# a405-diode-distortion.net
KiCad netlist of a schematic drawn in EAGLE
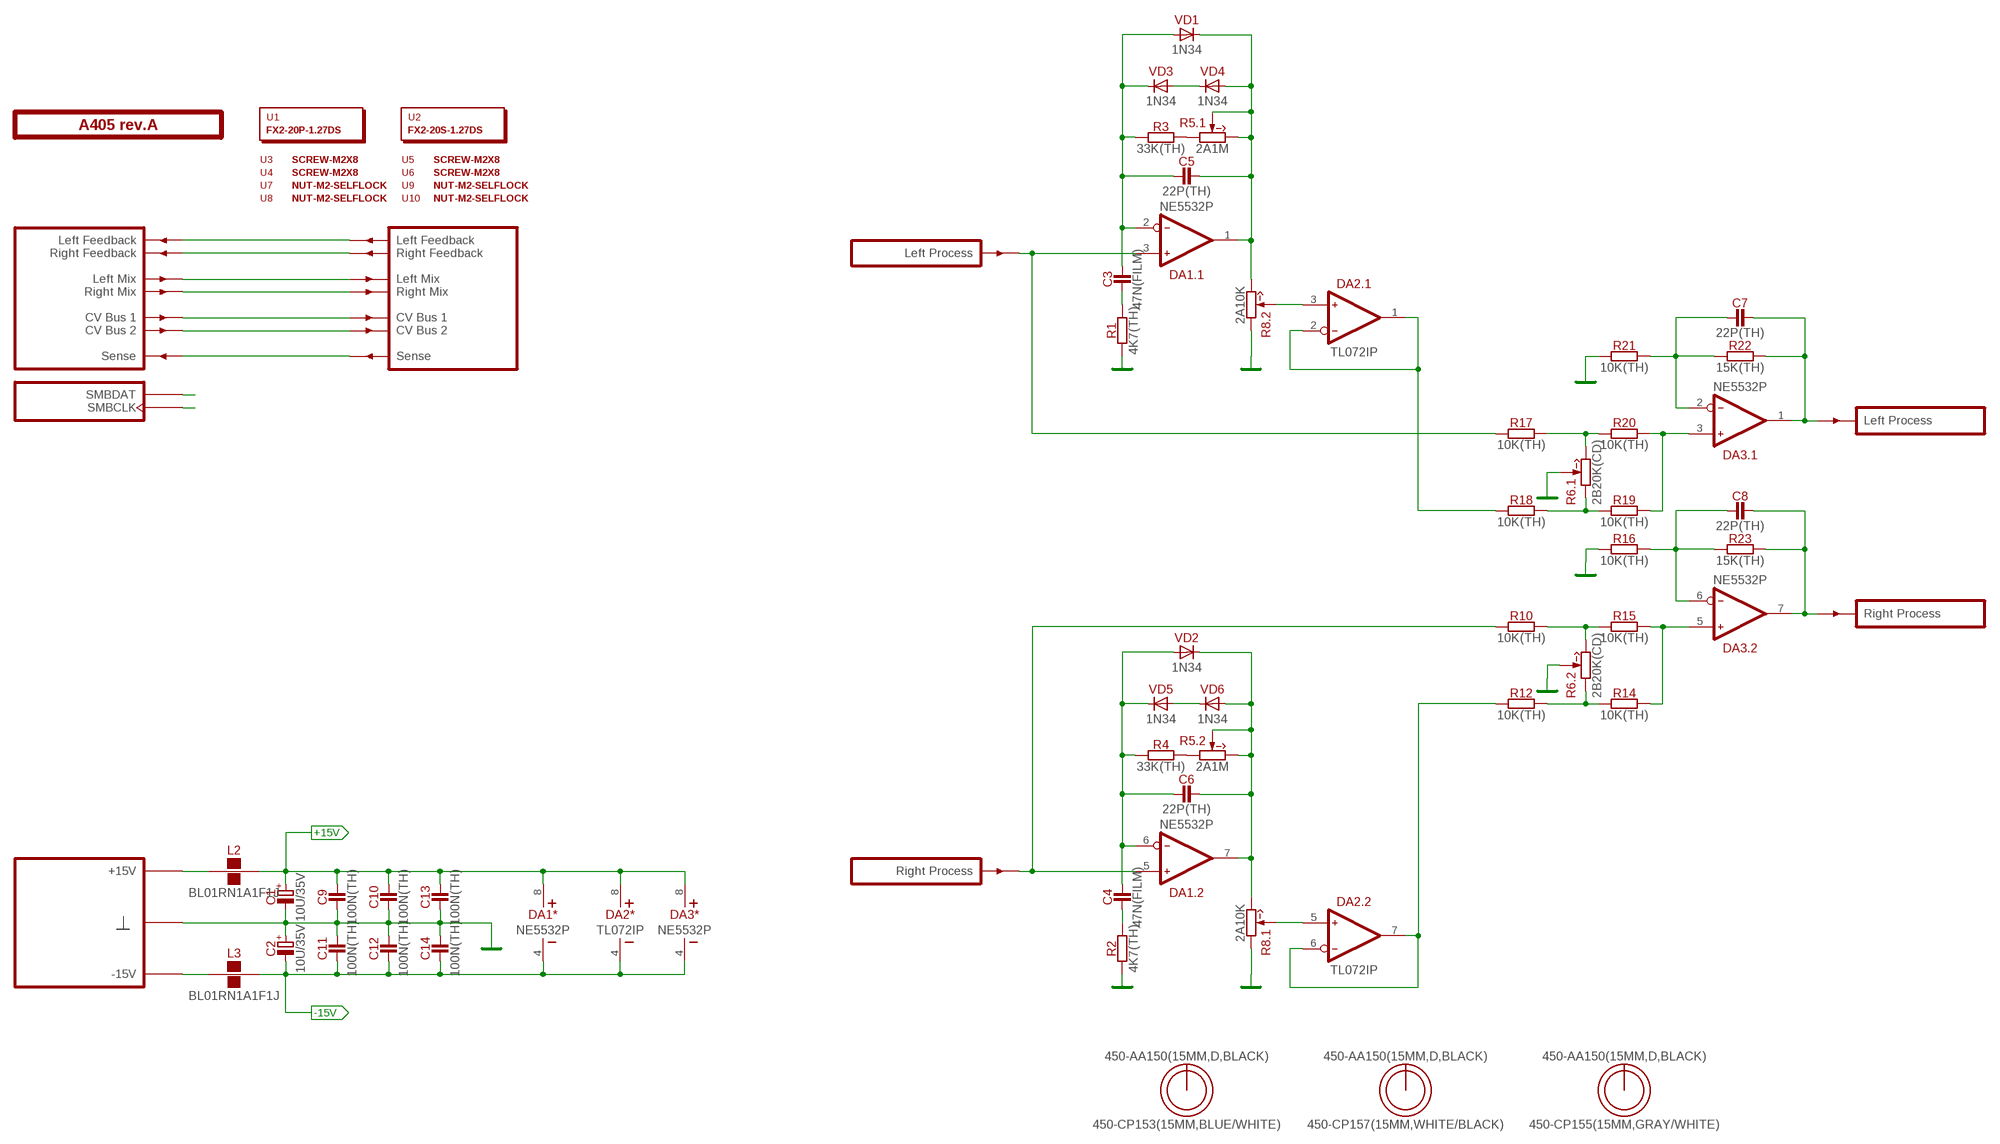
[diagram p0: schematic, sheet 1]

(export (version "E")
  (design (tool "Eeschema 10.0.6"))
  (components
    (comp (ref "C1")
      (value "10U/35V")
      (footprint "eagle-import:E2-5")
      (libsource (lib "eagle-import") (part "?10U/35V"))
    )
    (comp (ref "C2")
      (value "10U/35V")
      (footprint "eagle-import:E2-5")
      (libsource (lib "eagle-import") (part "?10U/35V"))
    )
    (comp (ref "C3")
      (value "47N(FILM)")
      (footprint "eagle-import:C050-025X075")
      (libsource (lib "eagle-import") (part "?47N(FILM)"))
    )
    (comp (ref "C4")
      (value "47N(FILM)")
      (footprint "eagle-import:C050-025X075")
      (libsource (lib "eagle-import") (part "?47N(FILM)"))
    )
    (comp (ref "C5")
      (value "22P(TH)")
      (footprint "eagle-import:C050-024X044")
      (libsource (lib "eagle-import") (part "?22P(TH)"))
    )
    (comp (ref "C6")
      (value "22P(TH)")
      (footprint "eagle-import:C050-024X044")
      (libsource (lib "eagle-import") (part "?22P(TH)"))
    )
    (comp (ref "C7")
      (value "22P(TH)")
      (footprint "eagle-import:C050-024X044")
      (libsource (lib "eagle-import") (part "?22P(TH)"))
    )
    (comp (ref "C8")
      (value "22P(TH)")
      (footprint "eagle-import:C050-024X044")
      (libsource (lib "eagle-import") (part "?22P(TH)"))
    )
    (comp (ref "C9")
      (value "100N(TH)")
      (footprint "eagle-import:C050-024X044")
      (libsource (lib "eagle-import") (part "?100N(TH)"))
    )
    (comp (ref "C10")
      (value "100N(TH)")
      (footprint "eagle-import:C050-024X044")
      (libsource (lib "eagle-import") (part "?100N(TH)"))
    )
    (comp (ref "C11")
      (value "100N(TH)")
      (footprint "eagle-import:C050-024X044")
      (libsource (lib "eagle-import") (part "?100N(TH)"))
    )
    (comp (ref "C12")
      (value "100N(TH)")
      (footprint "eagle-import:C050-024X044")
      (libsource (lib "eagle-import") (part "?100N(TH)"))
    )
    (comp (ref "C13")
      (value "100N(TH)")
      (footprint "eagle-import:C050-024X044")
      (libsource (lib "eagle-import") (part "?100N(TH)"))
    )
    (comp (ref "C14")
      (value "100N(TH)")
      (footprint "eagle-import:C050-024X044")
      (libsource (lib "eagle-import") (part "?100N(TH)"))
    )
    (comp (ref "DA1")
      (value "NE5532P")
      (footprint "eagle-import:DIP-8")
      (libsource (lib "eagle-import") (part "NE5532P"))
    )
    (comp (ref "DA2")
      (value "TL072IP")
      (footprint "eagle-import:DIP-8")
      (libsource (lib "eagle-import") (part "TL072IP"))
    )
    (comp (ref "DA3")
      (value "NE5532P")
      (footprint "eagle-import:DIP-8")
      (libsource (lib "eagle-import") (part "NE5532P"))
    )
    (comp (ref "L2")
      (value "BL01RN1A1F1J")
      (footprint "eagle-import:BL01RN1A")
      (libsource (lib "eagle-import") (part "BL01RN1A?1F1J"))
    )
    (comp (ref "L3")
      (value "BL01RN1A1F1J")
      (footprint "eagle-import:BL01RN1A")
      (libsource (lib "eagle-import") (part "BL01RN1A?1F1J"))
    )
    (comp (ref "O2")
      (value "450-AA150(15MM,D,BLACK)")
      (footprint "eagle-import:EMPTY")
      (libsource (lib "eagle-import") (part "450-AA?150(15MM,D,BLACK)"))
    )
    (comp (ref "O3")
      (value "450-AA150(15MM,D,BLACK)")
      (footprint "eagle-import:EMPTY")
      (libsource (lib "eagle-import") (part "450-AA?150(15MM,D,BLACK)"))
    )
    (comp (ref "O4")
      (value "450-AA150(15MM,D,BLACK)")
      (footprint "eagle-import:EMPTY")
      (libsource (lib "eagle-import") (part "450-AA?150(15MM,D,BLACK)"))
    )
    (comp (ref "O5")
      (value "450-CP155(15MM,GRAY/WHITE)")
      (footprint "eagle-import:EMPTY")
      (libsource (lib "eagle-import") (part "450-C?P155(15MM,GRAY/WHITE)"))
    )
    (comp (ref "O6")
      (value "450-CP157(15MM,WHITE/BLACK)")
      (footprint "eagle-import:EMPTY")
      (libsource (lib "eagle-import") (part "450-C?P157(15MM,WHITE/BLACK)"))
    )
    (comp (ref "O7")
      (value "450-CP153(15MM,BLUE/WHITE)")
      (footprint "eagle-import:EMPTY")
      (libsource (lib "eagle-import") (part "450-C?P153(15MM,BLUE/WHITE)"))
    )
    (comp (ref "PCB1")
      (value "A405 rev.A")
      (footprint "eagle-import:ST2-BOARD-50")
      (libsource (lib "eagle-import") (part "ST2-BOARD-?50"))
    )
    (comp (ref "R1")
      (value "4K7(TH)")
      (footprint "eagle-import:R-0207_10")
      (libsource (lib "eagle-import") (part "?4K7(TH)"))
    )
    (comp (ref "R2")
      (value "4K7(TH)")
      (footprint "eagle-import:R-0207_10")
      (libsource (lib "eagle-import") (part "?4K7(TH)"))
    )
    (comp (ref "R3")
      (value "33K(TH)")
      (footprint "eagle-import:R-0207_10")
      (libsource (lib "eagle-import") (part "?33K(TH)"))
    )
    (comp (ref "R4")
      (value "33K(TH)")
      (footprint "eagle-import:R-0207_10")
      (libsource (lib "eagle-import") (part "?33K(TH)"))
    )
    (comp (ref "R5")
      (value "2A1M")
      (footprint "eagle-import:RV11-DUAL")
      (libsource (lib "eagle-import") (part "2?A1M"))
    )
    (comp (ref "R6")
      (value "2B20K(CD)")
      (footprint "eagle-import:RV11-DUAL")
      (libsource (lib "eagle-import") (part "2?B20K(CD)"))
    )
    (comp (ref "R8")
      (value "2A10K")
      (footprint "eagle-import:RV11-DUAL")
      (libsource (lib "eagle-import") (part "2?A10K"))
    )
    (comp (ref "R10")
      (value "10K(TH)")
      (footprint "eagle-import:R-0207_10")
      (libsource (lib "eagle-import") (part "?10K(TH)"))
    )
    (comp (ref "R12")
      (value "10K(TH)")
      (footprint "eagle-import:R-0207_10")
      (libsource (lib "eagle-import") (part "?10K(TH)"))
    )
    (comp (ref "R14")
      (value "10K(TH)")
      (footprint "eagle-import:R-0207_10")
      (libsource (lib "eagle-import") (part "?10K(TH)"))
    )
    (comp (ref "R15")
      (value "10K(TH)")
      (footprint "eagle-import:R-0207_10")
      (libsource (lib "eagle-import") (part "?10K(TH)"))
    )
    (comp (ref "R16")
      (value "10K(TH)")
      (footprint "eagle-import:R-0207_10")
      (libsource (lib "eagle-import") (part "?10K(TH)"))
    )
    (comp (ref "R17")
      (value "10K(TH)")
      (footprint "eagle-import:R-0207_10")
      (libsource (lib "eagle-import") (part "?10K(TH)"))
    )
    (comp (ref "R18")
      (value "10K(TH)")
      (footprint "eagle-import:R-0207_10")
      (libsource (lib "eagle-import") (part "?10K(TH)"))
    )
    (comp (ref "R19")
      (value "10K(TH)")
      (footprint "eagle-import:R-0207_10")
      (libsource (lib "eagle-import") (part "?10K(TH)"))
    )
    (comp (ref "R20")
      (value "10K(TH)")
      (footprint "eagle-import:R-0207_10")
      (libsource (lib "eagle-import") (part "?10K(TH)"))
    )
    (comp (ref "R21")
      (value "10K(TH)")
      (footprint "eagle-import:R-0207_10")
      (libsource (lib "eagle-import") (part "?10K(TH)"))
    )
    (comp (ref "R22")
      (value "15K(TH)")
      (footprint "eagle-import:R-0207_10")
      (libsource (lib "eagle-import") (part "?15K(TH)"))
    )
    (comp (ref "R23")
      (value "15K(TH)")
      (footprint "eagle-import:R-0207_10")
      (libsource (lib "eagle-import") (part "?15K(TH)"))
    )
    (comp (ref "U1")
      (value "FX2-20P-1.27DS")
      (footprint "eagle-import:EMPTY")
      (libsource (lib "eagle-import") (part "?FX2-20P-1.27DS"))
    )
    (comp (ref "U2")
      (value "FX2-20S-1.27DS")
      (footprint "eagle-import:EMPTY")
      (libsource (lib "eagle-import") (part "?FX2-20S-1.27DS"))
    )
    (comp (ref "U3")
      (value "SCREW-M2X8")
      (footprint "eagle-import:EMPTY")
      (libsource (lib "eagle-import") (part "?SCREW-M2X8"))
    )
    (comp (ref "U4")
      (value "SCREW-M2X8")
      (footprint "eagle-import:EMPTY")
      (libsource (lib "eagle-import") (part "?SCREW-M2X8"))
    )
    (comp (ref "U5")
      (value "SCREW-M2X8")
      (footprint "eagle-import:EMPTY")
      (libsource (lib "eagle-import") (part "?SCREW-M2X8"))
    )
    (comp (ref "U6")
      (value "SCREW-M2X8")
      (footprint "eagle-import:EMPTY")
      (libsource (lib "eagle-import") (part "?SCREW-M2X8"))
    )
    (comp (ref "U7")
      (value "NUT-M2-SELFLOCK")
      (footprint "eagle-import:EMPTY")
      (libsource (lib "eagle-import") (part "?NUT-M2-SELFLOCK"))
    )
    (comp (ref "U8")
      (value "NUT-M2-SELFLOCK")
      (footprint "eagle-import:EMPTY")
      (libsource (lib "eagle-import") (part "?NUT-M2-SELFLOCK"))
    )
    (comp (ref "U9")
      (value "NUT-M2-SELFLOCK")
      (footprint "eagle-import:EMPTY")
      (libsource (lib "eagle-import") (part "?NUT-M2-SELFLOCK"))
    )
    (comp (ref "U10")
      (value "NUT-M2-SELFLOCK")
      (footprint "eagle-import:EMPTY")
      (libsource (lib "eagle-import") (part "?NUT-M2-SELFLOCK"))
    )
    (comp (ref "VD1")
      (value "1N34")
      (footprint "eagle-import:DO35-15")
      (libsource (lib "eagle-import") (part "?1N34"))
    )
    (comp (ref "VD2")
      (value "1N34")
      (footprint "eagle-import:DO35-15")
      (libsource (lib "eagle-import") (part "?1N34"))
    )
    (comp (ref "VD3")
      (value "1N34")
      (footprint "eagle-import:DO35-15")
      (libsource (lib "eagle-import") (part "?1N34"))
    )
    (comp (ref "VD4")
      (value "1N34")
      (footprint "eagle-import:DO35-15")
      (libsource (lib "eagle-import") (part "?1N34"))
    )
    (comp (ref "VD5")
      (value "1N34")
      (footprint "eagle-import:DO35-15")
      (libsource (lib "eagle-import") (part "?1N34"))
    )
    (comp (ref "VD6")
      (value "1N34")
      (footprint "eagle-import:DO35-15")
      (libsource (lib "eagle-import") (part "?1N34"))
    )
  )
  (nets
    (net (code "1") (name "+15V") (class "Default")
      (node (ref "C1") (pin "+") (pinfunction "+_+") (pintype "passive"))
      (node (ref "C10") (pin "2") (pinfunction "2_2") (pintype "passive"))
      (node (ref "C13") (pin "2") (pinfunction "2_2") (pintype "passive"))
      (node (ref "C9") (pin "2") (pinfunction "2_2") (pintype "passive"))
      (node (ref "DA1") (pin "8") (pinfunction "V+_8") (pintype "power_in"))
      (node (ref "DA2") (pin "8") (pinfunction "V+_8") (pintype "power_in"))
      (node (ref "DA3") (pin "8") (pinfunction "V+_8") (pintype "power_in"))
      (node (ref "L2") (pin "2") (pinfunction "2_2") (pintype "passive"))
    )
    (net (code "2") (name "-15V") (class "Default")
      (node (ref "C11") (pin "1") (pinfunction "1_1") (pintype "passive"))
      (node (ref "C12") (pin "1") (pinfunction "1_1") (pintype "passive"))
      (node (ref "C14") (pin "1") (pinfunction "1_1") (pintype "passive"))
      (node (ref "C2") (pin "-") (pinfunction "-_-") (pintype "passive"))
      (node (ref "DA1") (pin "4") (pinfunction "V-_4") (pintype "power_in"))
      (node (ref "DA2") (pin "4") (pinfunction "V-_4") (pintype "power_in"))
      (node (ref "DA3") (pin "4") (pinfunction "V-_4") (pintype "power_in"))
      (node (ref "L3") (pin "2") (pinfunction "2_2") (pintype "passive"))
    )
    (net (code "3") (name "GND") (class "Default")
      (node (ref "C1") (pin "-") (pinfunction "-_-") (pintype "passive"))
      (node (ref "C10") (pin "1") (pinfunction "1_1") (pintype "passive"))
      (node (ref "C11") (pin "2") (pinfunction "2_2") (pintype "passive"))
      (node (ref "C12") (pin "2") (pinfunction "2_2") (pintype "passive"))
      (node (ref "C13") (pin "1") (pinfunction "1_1") (pintype "passive"))
      (node (ref "C14") (pin "2") (pinfunction "2_2") (pintype "passive"))
      (node (ref "C2") (pin "+") (pinfunction "+_+") (pintype "passive"))
      (node (ref "C9") (pin "1") (pinfunction "1_1") (pintype "passive"))
      (node (ref "PCB1") (pin "B4") (pinfunction "GND_B4") (pintype "bidirectional"))
      (node (ref "PCB1") (pin "B4'") (pinfunction "GND_B4'") (pintype "bidirectional"))
      (node (ref "PCB1") (pin "B5") (pinfunction "GND_B5") (pintype "bidirectional"))
      (node (ref "PCB1") (pin "B5'") (pinfunction "GND_B5'") (pintype "bidirectional"))
      (node (ref "PCB1") (pin "B6") (pinfunction "GND_B6") (pintype "bidirectional"))
      (node (ref "PCB1") (pin "B6'") (pinfunction "GND_B6'") (pintype "bidirectional"))
      (node (ref "PCB1") (pin "B7") (pinfunction "GND_B7") (pintype "bidirectional"))
      (node (ref "PCB1") (pin "B7'") (pinfunction "GND_B7'") (pintype "bidirectional"))
      (node (ref "PCB1") (pin "B8") (pinfunction "GND_B8") (pintype "bidirectional"))
      (node (ref "PCB1") (pin "B8'") (pinfunction "GND_B8'") (pintype "bidirectional"))
      (node (ref "R1") (pin "1") (pinfunction "1_1") (pintype "passive"))
      (node (ref "R16") (pin "1") (pinfunction "1_1") (pintype "passive"))
      (node (ref "R2") (pin "1") (pinfunction "1_1") (pintype "passive"))
      (node (ref "R21") (pin "1") (pinfunction "1_1") (pintype "passive"))
      (node (ref "R6") (pin "2") (pinfunction "W_2") (pintype "passive"))
      (node (ref "R6") (pin "2'") (pinfunction "W_2'") (pintype "passive"))
      (node (ref "R8") (pin "1") (pinfunction "CCW_1") (pintype "passive"))
      (node (ref "R8") (pin "1'") (pinfunction "CCW_1'") (pintype "passive"))
    )
    (net (code "4") (name "Net-(C3-Pad1)") (class "Default")
      (node (ref "C3") (pin "1") (pinfunction "1_1") (pintype "passive"))
      (node (ref "R1") (pin "2") (pinfunction "2_2") (pintype "passive"))
    )
    (net (code "5") (name "Net-(C4-Pad1)") (class "Default")
      (node (ref "C4") (pin "1") (pinfunction "1_1") (pintype "passive"))
      (node (ref "R2") (pin "2") (pinfunction "2_2") (pintype "passive"))
    )
    (net (code "6") (name "Net-(DA1B-IN+)") (class "Default")
      (node (ref "DA1") (pin "3") (pinfunction "IN+_3") (pintype "input"))
      (node (ref "PCB1") (pin "BINL") (pinfunction "INL_BINL") (pintype "bidirectional"))
      (node (ref "R17") (pin "1") (pinfunction "1_1") (pintype "passive"))
    )
    (net (code "7") (name "Net-(DA1B-IN-)") (class "Default")
      (node (ref "C3") (pin "2") (pinfunction "2_2") (pintype "passive"))
      (node (ref "C5") (pin "1") (pinfunction "1_1") (pintype "passive"))
      (node (ref "DA1") (pin "2") (pinfunction "IN-_2") (pintype "input"))
      (node (ref "R3") (pin "1") (pinfunction "1_1") (pintype "passive"))
      (node (ref "VD1") (pin "A") (pinfunction "A_A") (pintype "passive"))
      (node (ref "VD3") (pin "C") (pinfunction "C_C") (pintype "passive"))
    )
    (net (code "8") (name "Net-(DA1B-OUT)") (class "Default")
      (node (ref "C5") (pin "2") (pinfunction "2_2") (pintype "passive"))
      (node (ref "DA1") (pin "1") (pinfunction "OUT_1") (pintype "output"))
      (node (ref "R5") (pin "2") (pinfunction "W_2") (pintype "passive"))
      (node (ref "R5") (pin "3") (pinfunction "CW_3") (pintype "passive"))
      (node (ref "R8") (pin "3'") (pinfunction "CW_3'") (pintype "passive"))
      (node (ref "VD1") (pin "C") (pinfunction "C_C") (pintype "passive"))
      (node (ref "VD4") (pin "A") (pinfunction "A_A") (pintype "passive"))
    )
    (net (code "9") (name "Net-(DA1C-IN+)") (class "Default")
      (node (ref "DA1") (pin "5") (pinfunction "IN+_5") (pintype "input"))
      (node (ref "PCB1") (pin "BINR") (pinfunction "INR_BINR") (pintype "bidirectional"))
      (node (ref "R10") (pin "1") (pinfunction "1_1") (pintype "passive"))
    )
    (net (code "10") (name "Net-(DA1C-IN-)") (class "Default")
      (node (ref "C4") (pin "2") (pinfunction "2_2") (pintype "passive"))
      (node (ref "C6") (pin "1") (pinfunction "1_1") (pintype "passive"))
      (node (ref "DA1") (pin "6") (pinfunction "IN-_6") (pintype "input"))
      (node (ref "R4") (pin "1") (pinfunction "1_1") (pintype "passive"))
      (node (ref "VD2") (pin "A") (pinfunction "A_A") (pintype "passive"))
      (node (ref "VD5") (pin "C") (pinfunction "C_C") (pintype "passive"))
    )
    (net (code "11") (name "Net-(DA1C-OUT)") (class "Default")
      (node (ref "C6") (pin "2") (pinfunction "2_2") (pintype "passive"))
      (node (ref "DA1") (pin "7") (pinfunction "OUT_7") (pintype "output"))
      (node (ref "R5") (pin "2'") (pinfunction "W_2'") (pintype "passive"))
      (node (ref "R5") (pin "3'") (pinfunction "CW_3'") (pintype "passive"))
      (node (ref "R8") (pin "3") (pinfunction "CW_3") (pintype "passive"))
      (node (ref "VD2") (pin "C") (pinfunction "C_C") (pintype "passive"))
      (node (ref "VD6") (pin "A") (pinfunction "A_A") (pintype "passive"))
    )
    (net (code "12") (name "Net-(DA2B-IN+)") (class "Default")
      (node (ref "DA2") (pin "3") (pinfunction "IN+_3") (pintype "input"))
      (node (ref "R8") (pin "2'") (pinfunction "W_2'") (pintype "passive"))
    )
    (net (code "13") (name "Net-(DA2B-IN-)") (class "Default")
      (node (ref "DA2") (pin "1") (pinfunction "OUT_1") (pintype "output"))
      (node (ref "DA2") (pin "2") (pinfunction "IN-_2") (pintype "input"))
      (node (ref "R18") (pin "1") (pinfunction "1_1") (pintype "passive"))
    )
    (net (code "14") (name "Net-(DA2C-IN+)") (class "Default")
      (node (ref "DA2") (pin "5") (pinfunction "IN+_5") (pintype "input"))
      (node (ref "R8") (pin "2") (pinfunction "W_2") (pintype "passive"))
    )
    (net (code "15") (name "Net-(DA2C-IN-)") (class "Default")
      (node (ref "DA2") (pin "6") (pinfunction "IN-_6") (pintype "input"))
      (node (ref "DA2") (pin "7") (pinfunction "OUT_7") (pintype "output"))
      (node (ref "R12") (pin "1") (pinfunction "1_1") (pintype "passive"))
    )
    (net (code "16") (name "Net-(DA3B-IN+)") (class "Default")
      (node (ref "DA3") (pin "3") (pinfunction "IN+_3") (pintype "input"))
      (node (ref "R19") (pin "2") (pinfunction "2_2") (pintype "passive"))
      (node (ref "R20") (pin "2") (pinfunction "2_2") (pintype "passive"))
    )
    (net (code "17") (name "Net-(DA3B-IN-)") (class "Default")
      (node (ref "C7") (pin "1") (pinfunction "1_1") (pintype "passive"))
      (node (ref "DA3") (pin "2") (pinfunction "IN-_2") (pintype "input"))
      (node (ref "R21") (pin "2") (pinfunction "2_2") (pintype "passive"))
      (node (ref "R22") (pin "1") (pinfunction "1_1") (pintype "passive"))
    )
    (net (code "18") (name "Net-(DA3B-OUT)") (class "Default")
      (node (ref "C7") (pin "2") (pinfunction "2_2") (pintype "passive"))
      (node (ref "DA3") (pin "1") (pinfunction "OUT_1") (pintype "output"))
      (node (ref "PCB1") (pin "BOUTL'") (pinfunction "OUTL_BOUTL'") (pintype "bidirectional"))
      (node (ref "R22") (pin "2") (pinfunction "2_2") (pintype "passive"))
    )
    (net (code "19") (name "Net-(DA3C-IN+)") (class "Default")
      (node (ref "DA3") (pin "5") (pinfunction "IN+_5") (pintype "input"))
      (node (ref "R14") (pin "2") (pinfunction "2_2") (pintype "passive"))
      (node (ref "R15") (pin "2") (pinfunction "2_2") (pintype "passive"))
    )
    (net (code "20") (name "Net-(DA3C-IN-)") (class "Default")
      (node (ref "C8") (pin "1") (pinfunction "1_1") (pintype "passive"))
      (node (ref "DA3") (pin "6") (pinfunction "IN-_6") (pintype "input"))
      (node (ref "R16") (pin "2") (pinfunction "2_2") (pintype "passive"))
      (node (ref "R23") (pin "1") (pinfunction "1_1") (pintype "passive"))
    )
    (net (code "21") (name "Net-(DA3C-OUT)") (class "Default")
      (node (ref "C8") (pin "2") (pinfunction "2_2") (pintype "passive"))
      (node (ref "DA3") (pin "7") (pinfunction "OUT_7") (pintype "output"))
      (node (ref "PCB1") (pin "BOUTR'") (pinfunction "OUTR_BOUTR'") (pintype "bidirectional"))
      (node (ref "R23") (pin "2") (pinfunction "2_2") (pintype "passive"))
    )
    (net (code "22") (name "Net-(L2-Pad1)") (class "Default")
      (node (ref "L2") (pin "1") (pinfunction "1_1") (pintype "passive"))
      (node (ref "PCB1") (pin "A+15") (pinfunction "P+15V_A+15") (pintype "bidirectional"))
      (node (ref "PCB1") (pin "A+15'") (pinfunction "P+15V_A+15'") (pintype "bidirectional"))
      (node (ref "PCB1") (pin "B+15") (pinfunction "P+15V_B+15") (pintype "bidirectional"))
      (node (ref "PCB1") (pin "B+15'") (pinfunction "P+15V_B+15'") (pintype "bidirectional"))
    )
    (net (code "23") (name "Net-(L3-Pad1)") (class "Default")
      (node (ref "L3") (pin "1") (pinfunction "1_1") (pintype "passive"))
      (node (ref "PCB1") (pin "A-15") (pinfunction "P-15V_A-15") (pintype "bidirectional"))
      (node (ref "PCB1") (pin "A-15'") (pinfunction "P-15V_A-15'") (pintype "bidirectional"))
      (node (ref "PCB1") (pin "B-15") (pinfunction "P-15V_B-15") (pintype "bidirectional"))
      (node (ref "PCB1") (pin "B-15'") (pinfunction "P-15V_B-15'") (pintype "bidirectional"))
    )
    (net (code "24") (name "Net-(PCB1F-CV1)") (class "Default")
      (node (ref "PCB1") (pin "ACV1") (pinfunction "CV1_ACV1") (pintype "bidirectional"))
      (node (ref "PCB1") (pin "ACV1'") (pinfunction "CV1'_ACV1'") (pintype "bidirectional"))
    )
    (net (code "25") (name "Net-(PCB1F-CV2)") (class "Default")
      (node (ref "PCB1") (pin "ACV2") (pinfunction "CV2_ACV2") (pintype "bidirectional"))
      (node (ref "PCB1") (pin "ACV2'") (pinfunction "CV2'_ACV2'") (pintype "bidirectional"))
    )
    (net (code "26") (name "Net-(PCB1F-LFBK)") (class "Default")
      (node (ref "PCB1") (pin "ALFBK") (pinfunction "LFBK_ALFBK") (pintype "bidirectional"))
      (node (ref "PCB1") (pin "ALFBK'") (pinfunction "LFBK'_ALFBK'") (pintype "bidirectional"))
    )
    (net (code "27") (name "Net-(PCB1F-LMIX)") (class "Default")
      (node (ref "PCB1") (pin "ALMIX") (pinfunction "LMIX_ALMIX") (pintype "bidirectional"))
      (node (ref "PCB1") (pin "ALMIX'") (pinfunction "LMIX'_ALMIX'") (pintype "bidirectional"))
    )
    (net (code "28") (name "Net-(PCB1F-RFBK)") (class "Default")
      (node (ref "PCB1") (pin "ARFBK") (pinfunction "RFBK_ARFBK") (pintype "bidirectional"))
      (node (ref "PCB1") (pin "ARFBK'") (pinfunction "RFBK'_ARFBK'") (pintype "bidirectional"))
    )
    (net (code "29") (name "Net-(PCB1F-RMIX)") (class "Default")
      (node (ref "PCB1") (pin "ARMIX") (pinfunction "RMIX_ARMIX") (pintype "bidirectional"))
      (node (ref "PCB1") (pin "ARMIX'") (pinfunction "RMIX'_ARMIX'") (pintype "bidirectional"))
    )
    (net (code "30") (name "Net-(PCB1F-SENSE)") (class "Default")
      (node (ref "PCB1") (pin "BSENSE") (pinfunction "SENSE_BSENSE") (pintype "bidirectional"))
      (node (ref "PCB1") (pin "BSENSE'") (pinfunction "SENSE'_BSENSE'") (pintype "bidirectional"))
    )
    (net (code "31") (name "Net-(PCB1H-SMBCLK-PadASMBCLK')") (class "Default")
      (node (ref "PCB1") (pin "ASMBCLK") (pinfunction "SMBCLK_ASMBCLK") (pintype "bidirectional"))
      (node (ref "PCB1") (pin "ASMBCLK'") (pinfunction "SMBCLK_ASMBCLK'") (pintype "bidirectional"))
    )
    (net (code "32") (name "Net-(PCB1H-SMBDAT-PadASMBDAT')") (class "Default")
      (node (ref "PCB1") (pin "ASMBDAT") (pinfunction "SMBDAT_ASMBDAT") (pintype "bidirectional"))
      (node (ref "PCB1") (pin "ASMBDAT'") (pinfunction "SMBDAT_ASMBDAT'") (pintype "bidirectional"))
    )
    (net (code "33") (name "Net-(R5A-CCW)") (class "Default")
      (node (ref "R3") (pin "2") (pinfunction "2_2") (pintype "passive"))
      (node (ref "R5") (pin "1") (pinfunction "CCW_1") (pintype "passive"))
    )
    (net (code "34") (name "Net-(R5B-CCW)") (class "Default")
      (node (ref "R4") (pin "2") (pinfunction "2_2") (pintype "passive"))
      (node (ref "R5") (pin "1'") (pinfunction "CCW_1'") (pintype "passive"))
    )
    (net (code "35") (name "Net-(R6A-CCW)") (class "Default")
      (node (ref "R18") (pin "2") (pinfunction "2_2") (pintype "passive"))
      (node (ref "R19") (pin "1") (pinfunction "1_1") (pintype "passive"))
      (node (ref "R6") (pin "1") (pinfunction "CCW_1") (pintype "passive"))
    )
    (net (code "36") (name "Net-(R6A-CW)") (class "Default")
      (node (ref "R17") (pin "2") (pinfunction "2_2") (pintype "passive"))
      (node (ref "R20") (pin "1") (pinfunction "1_1") (pintype "passive"))
      (node (ref "R6") (pin "3") (pinfunction "CW_3") (pintype "passive"))
    )
    (net (code "37") (name "Net-(R6B-CCW)") (class "Default")
      (node (ref "R12") (pin "2") (pinfunction "2_2") (pintype "passive"))
      (node (ref "R14") (pin "1") (pinfunction "1_1") (pintype "passive"))
      (node (ref "R6") (pin "1'") (pinfunction "CCW_1'") (pintype "passive"))
    )
    (net (code "38") (name "Net-(R6B-CW)") (class "Default")
      (node (ref "R10") (pin "2") (pinfunction "2_2") (pintype "passive"))
      (node (ref "R15") (pin "1") (pinfunction "1_1") (pintype "passive"))
      (node (ref "R6") (pin "3'") (pinfunction "CW_3'") (pintype "passive"))
    )
    (net (code "39") (name "Net-(VD3-PadA)") (class "Default")
      (node (ref "VD3") (pin "A") (pinfunction "A_A") (pintype "passive"))
      (node (ref "VD4") (pin "C") (pinfunction "C_C") (pintype "passive"))
    )
    (net (code "40") (name "Net-(VD5-PadA)") (class "Default")
      (node (ref "VD5") (pin "A") (pinfunction "A_A") (pintype "passive"))
      (node (ref "VD6") (pin "C") (pinfunction "C_C") (pintype "passive"))
    )
  )
)
